# rgb_circuit_diagram.net
KiCad netlist of a schematic drawn in EAGLE
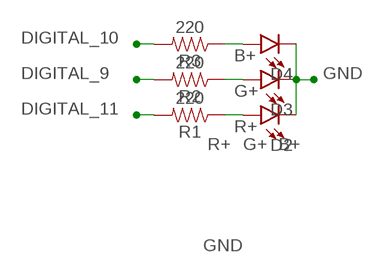
[diagram p0: schematic, sheet 1]

(export (version "E")
  (design (tool "Eeschema 10.0.6"))
  (components
    (comp (ref "D2")
      (value "LED-3MM-NO_SILK")
      (footprint "eagle-import:LED_3MM-NS")
      (libsource (lib "eagle-import") (part "LED-3MM-NO_SILK"))
    )
    (comp (ref "D3")
      (value "LED-3MM-NO_SILK")
      (footprint "eagle-import:LED_3MM-NS")
      (libsource (lib "eagle-import") (part "LED-3MM-NO_SILK"))
    )
    (comp (ref "D4")
      (value "LED-3MM-NO_SILK")
      (footprint "eagle-import:LED_3MM-NS")
      (libsource (lib "eagle-import") (part "LED-3MM-NO_SILK"))
    )
    (comp (ref "R1")
      (value "220")
      (footprint "eagle-import:0603")
      (libsource (lib "eagle-import") (part "220OHM-0603-1/10W-1%"))
    )
    (comp (ref "R2")
      (value "220")
      (footprint "eagle-import:0603")
      (libsource (lib "eagle-import") (part "220OHM-0603-1/10W-1%"))
    )
    (comp (ref "R3")
      (value "220")
      (footprint "eagle-import:0603")
      (libsource (lib "eagle-import") (part "220OHM-0603-1/10W-1%"))
    )
  )
  (nets
    (net (code "1") (name "/B+") (class "Default")
      (node (ref "D4") (pin "A") (pinfunction "A_A") (pintype "passive"))
      (node (ref "R3") (pin "1") (pinfunction "1_1") (pintype "passive"))
    )
    (net (code "2") (name "/DIGITAL_9") (class "Default")
      (node (ref "R2") (pin "2") (pinfunction "2_2") (pintype "passive"))
    )
    (net (code "3") (name "/DIGITAL_10") (class "Default")
      (node (ref "R3") (pin "2") (pinfunction "2_2") (pintype "passive"))
    )
    (net (code "4") (name "/DIGITAL_11") (class "Default")
      (node (ref "R1") (pin "2") (pinfunction "2_2") (pintype "passive"))
    )
    (net (code "5") (name "/G+") (class "Default")
      (node (ref "D3") (pin "A") (pinfunction "A_A") (pintype "passive"))
      (node (ref "R2") (pin "1") (pinfunction "1_1") (pintype "passive"))
    )
    (net (code "6") (name "/GND") (class "Default")
      (node (ref "D2") (pin "K") (pinfunction "C_K") (pintype "passive"))
      (node (ref "D3") (pin "K") (pinfunction "C_K") (pintype "passive"))
      (node (ref "D4") (pin "K") (pinfunction "C_K") (pintype "passive"))
    )
    (net (code "7") (name "/R+") (class "Default")
      (node (ref "D2") (pin "A") (pinfunction "A_A") (pintype "passive"))
      (node (ref "R1") (pin "1") (pinfunction "1_1") (pintype "passive"))
    )
  )
)
